# lab1_kondratchenko_usb_rs485.net
KiCad netlist of a schematic drawn in Altium Designer
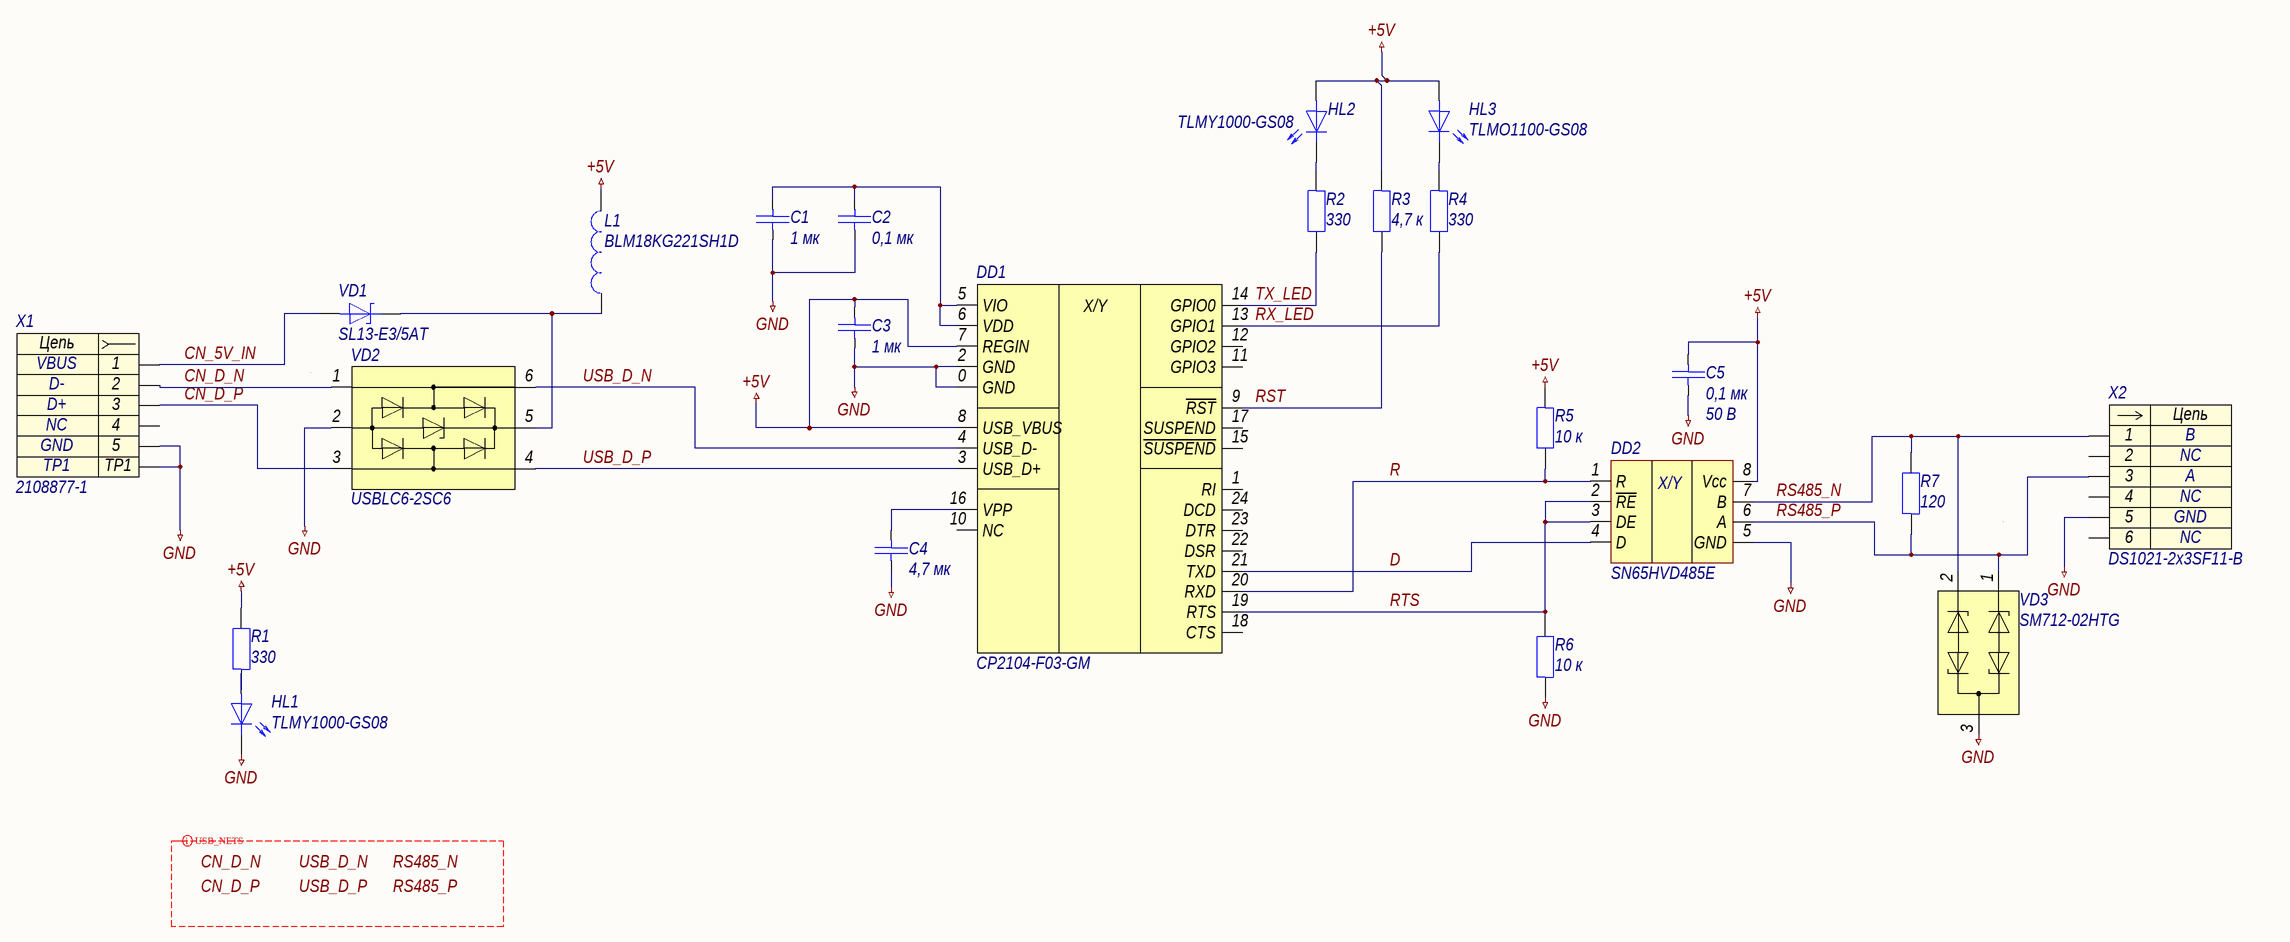
[diagram p0: lab1_kondratchenko_usb_rs485.SchDoc]

(export (version "E")
  (design (tool "Eeschema 10.0.6"))
  (components
    (comp (ref "C1")
      (value "1 мк")
      (footprint "C0603")
      (description "=Описание")
      (libsource (lib "Database_Students") (part "CAPACITOR-NONPOLAR"))
    )
    (comp (ref "C2")
      (value "0,1 мк")
      (footprint "C0603")
      (description "=Описание")
      (libsource (lib "Database_Students") (part "CAPACITOR-NONPOLAR"))
    )
    (comp (ref "C3")
      (value "1 мк")
      (footprint "C0603")
      (description "=Описание")
      (libsource (lib "Database_Students") (part "CAPACITOR-NONPOLAR"))
    )
    (comp (ref "C4")
      (value "4,7 мк")
      (footprint "C0603")
      (description "=Описание")
      (libsource (lib "Database_Students") (part "CAPACITOR-NONPOLAR"))
    )
    (comp (ref "C5")
      (value "0,1 мк")
      (footprint "C0603")
      (description "=Описание")
      (fields (field (name "НАПРЯЖЕНИЕ") "50 В"))
      (libsource (lib "Database_Students") (part "CAPACITOR-NONPOLAR"))
    )
    (comp (ref "DD1")
      (value "CP2104-F03-GM")
      (footprint "QFN-24-400X400X80")
      (description "=Описание")
      (libsource (lib "Database_Students") (part "CP2104-F03-GM"))
    )
    (comp (ref "DD2")
      (value "SN65HVD485E")
      (footprint "D0008A")
      (description "=Описание")
      (libsource (lib "SN65HVD485E") (part "SN65HVD485E"))
    )
    (comp (ref "HL1")
      (value "TLMY1000-GS08")
      (footprint "HL0603")
      (description "=Описание")
      (libsource (lib "Database_Students") (part "LED-COMMON"))
    )
    (comp (ref "HL2")
      (value "TLMY1000-GS08")
      (footprint "HL0603")
      (description "=Описание")
      (libsource (lib "Database_Students") (part "LED-COMMON"))
    )
    (comp (ref "HL3")
      (value "TLMO1100-GS08")
      (footprint "HL0603")
      (description "=Описание")
      (libsource (lib "Database_Students") (part "LED-COMMON"))
    )
    (comp (ref "L1")
      (value "BLM18KG221SH1D")
      (footprint "BLM-2-0603")
      (description "=Описание")
      (libsource (lib "Database_Students") (part "FERRITE-BEAD"))
    )
    (comp (ref "R1")
      (value "330")
      (footprint "R0603")
      (description "=Описание")
      (libsource (lib "Database_Students") (part "R-COMMON"))
    )
    (comp (ref "R2")
      (value "330")
      (footprint "R0603")
      (description "=Описание")
      (libsource (lib "Database_Students") (part "RESISTOR-COMMON"))
    )
    (comp (ref "R3")
      (value "4,7 к")
      (footprint "R0603")
      (description "=Описание")
      (libsource (lib "Database_Students") (part "RESISTOR-COMMON"))
    )
    (comp (ref "R4")
      (value "330")
      (footprint "R0603")
      (description "=Описание")
      (libsource (lib "Database_Students") (part "RESISTOR-COMMON"))
    )
    (comp (ref "R5")
      (value "10 к")
      (footprint "R0603")
      (description "=Описание")
      (libsource (lib "Database_Students") (part "RESISTOR-COMMON"))
    )
    (comp (ref "R6")
      (value "10 к")
      (footprint "R0603")
      (description "=Описание")
      (libsource (lib "Database_Students") (part "RESISTOR-COMMON"))
    )
    (comp (ref "R7")
      (value "120")
      (footprint "R0603")
      (description "=Описание")
      (libsource (lib "Database_Students") (part "R-COMMON"))
    )
    (comp (ref "VD1")
      (value "SL13-E3/5AT")
      (footprint "DO-214AC")
      (description "=Описание")
      (libsource (lib "Database_Students") (part "DIODE-SCHOTTKY"))
    )
    (comp (ref "VD2")
      (value "USBLC6-2SC6")
      (footprint "SOT-23-6")
      (description "=Описание")
      (libsource (lib "Database_Students") (part "USBLC6-2SC6"))
    )
    (comp (ref "VD3")
      (value "SM712-02HTG")
      (footprint "SOT-23-3")
      (description "=Описание")
      (libsource (lib "Database_Students") (part "SM712-02HTG"))
    )
    (comp (ref "X1")
      (value "2108877-1")
      (footprint "2108877-1")
      (libsource (lib "Database_Students") (part "HEADER-5-TP1-SCT"))
    )
    (comp (ref "X2")
      (value "DS1021-2x3SF11-B")
      (footprint "DS1021-2X3SF11-B")
      (description "=Описание")
      (libsource (lib "Database_Students") (part "HEADER-6-PLG"))
    )
  )
  (nets
    (net (code "1") (name "+5V") (class "Default")
      (node (ref "C3") (pin "2") (pinfunction "2_2") (pintype "passive"))
      (node (ref "C5") (pin "2") (pinfunction "2_2") (pintype "passive"))
      (node (ref "DD1") (pin "7") (pinfunction "REGIN_7") (pintype "passive"))
      (node (ref "DD1") (pin "8") (pinfunction "USB_VBUS_8") (pintype "passive"))
      (node (ref "DD2") (pin "8") (pinfunction "Vcc_8") (pintype "passive"))
      (node (ref "HL2") (pin "2") (pinfunction "2_2") (pintype "passive"))
      (node (ref "HL3") (pin "2") (pinfunction "2_2") (pintype "passive"))
      (node (ref "L1") (pin "2") (pinfunction "2_2") (pintype "passive"))
      (node (ref "R1") (pin "2") (pinfunction "2_2") (pintype "passive"))
      (node (ref "R3") (pin "1") (pinfunction "1_1") (pintype "passive"))
      (node (ref "R5") (pin "1") (pinfunction "1_1") (pintype "passive"))
    )
    (net (code "2") (name "/CN_5V_IN") (class "Default")
      (node (ref "VD1") (pin "2") (pinfunction "2_2") (pintype "passive"))
      (node (ref "X1") (pin "1") (pinfunction "1_1") (pintype "passive"))
    )
    (net (code "3") (name "/CN_D_N") (class "Default")
      (node (ref "VD2") (pin "1") (pinfunction "1_1") (pintype "passive"))
      (node (ref "X1") (pin "2") (pinfunction "2_2") (pintype "passive"))
    )
    (net (code "4") (name "/CN_D_P") (class "Default")
      (node (ref "VD2") (pin "3") (pinfunction "3_3") (pintype "passive"))
      (node (ref "X1") (pin "3") (pinfunction "3_3") (pintype "passive"))
    )
    (net (code "5") (name "/D") (class "Default")
      (node (ref "DD1") (pin "21") (pinfunction "TXD_21") (pintype "passive"))
      (node (ref "DD2") (pin "4") (pinfunction "D_4") (pintype "passive"))
    )
    (net (code "6") (name "/R") (class "Default")
      (node (ref "DD1") (pin "20") (pinfunction "RXD_20") (pintype "passive"))
      (node (ref "DD2") (pin "1") (pinfunction "R_1") (pintype "passive"))
      (node (ref "R5") (pin "2") (pinfunction "2_2") (pintype "passive"))
    )
    (net (code "7") (name "/RS485_N") (class "Default")
      (node (ref "DD2") (pin "7") (pinfunction "B_7") (pintype "passive"))
      (node (ref "R7") (pin "2") (pinfunction "2_2") (pintype "passive"))
      (node (ref "VD3") (pin "2") (pinfunction "2_2") (pintype "passive"))
      (node (ref "X2") (pin "1") (pinfunction "1_1") (pintype "passive"))
    )
    (net (code "8") (name "/RS485_P") (class "Default")
      (node (ref "DD2") (pin "6") (pinfunction "A_6") (pintype "passive"))
      (node (ref "R7") (pin "1") (pinfunction "1_1") (pintype "passive"))
      (node (ref "VD3") (pin "1") (pinfunction "1_1") (pintype "passive"))
      (node (ref "X2") (pin "3") (pinfunction "3_3") (pintype "passive"))
    )
    (net (code "9") (name "/RST") (class "Default")
      (node (ref "DD1") (pin "9") (pinfunction "~{RST}_9") (pintype "passive"))
      (node (ref "R3") (pin "2") (pinfunction "2_2") (pintype "passive"))
    )
    (net (code "10") (name "/RTS") (class "Default")
      (node (ref "DD1") (pin "19") (pinfunction "RTS_19") (pintype "passive"))
      (node (ref "DD2") (pin "2") (pinfunction "~{RE}_2") (pintype "passive"))
      (node (ref "DD2") (pin "3") (pinfunction "DE_3") (pintype "passive"))
      (node (ref "R6") (pin "2") (pinfunction "2_2") (pintype "passive"))
    )
    (net (code "11") (name "/RX_LED") (class "Default")
      (node (ref "DD1") (pin "13") (pinfunction "GPIO1_13") (pintype "passive"))
      (node (ref "R4") (pin "2") (pinfunction "2_2") (pintype "passive"))
    )
    (net (code "12") (name "/TX_LED") (class "Default")
      (node (ref "DD1") (pin "14") (pinfunction "GPIO0_14") (pintype "passive"))
      (node (ref "R2") (pin "2") (pinfunction "2_2") (pintype "passive"))
    )
    (net (code "13") (name "/USB_D_N") (class "Default")
      (node (ref "DD1") (pin "4") (pinfunction "USB_D-_4") (pintype "passive"))
      (node (ref "VD2") (pin "6") (pinfunction "6_6") (pintype "passive"))
    )
    (net (code "14") (name "/USB_D_P") (class "Default")
      (node (ref "DD1") (pin "3") (pinfunction "USB_D+_3") (pintype "passive"))
      (node (ref "VD2") (pin "4") (pinfunction "4_4") (pintype "passive"))
    )
    (net (code "15") (name "GND") (class "Default")
      (node (ref "C1") (pin "1") (pinfunction "1_1") (pintype "passive"))
      (node (ref "C2") (pin "1") (pinfunction "1_1") (pintype "passive"))
      (node (ref "C3") (pin "1") (pinfunction "1_1") (pintype "passive"))
      (node (ref "C4") (pin "1") (pinfunction "1_1") (pintype "passive"))
      (node (ref "C5") (pin "1") (pinfunction "1_1") (pintype "passive"))
      (node (ref "DD1") (pin "0") (pinfunction "GND_0") (pintype "passive"))
      (node (ref "DD1") (pin "2") (pinfunction "GND_2") (pintype "passive"))
      (node (ref "DD2") (pin "5") (pinfunction "GND_5") (pintype "passive"))
      (node (ref "HL1") (pin "1") (pinfunction "1_1") (pintype "passive"))
      (node (ref "R6") (pin "1") (pinfunction "1_1") (pintype "passive"))
      (node (ref "VD2") (pin "2") (pinfunction "2_2") (pintype "passive"))
      (node (ref "VD3") (pin "3") (pinfunction "3_3") (pintype "passive"))
      (node (ref "X1") (pin "5") (pinfunction "5_5") (pintype "passive"))
      (node (ref "X1") (pin "TP1") (pinfunction "TP1_TP1") (pintype "passive"))
      (node (ref "X2") (pin "5") (pinfunction "5_5") (pintype "passive"))
    )
    (net (code "16") (name "Net-(DD1-VDD)") (class "Default")
      (node (ref "C1") (pin "2") (pinfunction "2_2") (pintype "passive"))
      (node (ref "C2") (pin "2") (pinfunction "2_2") (pintype "passive"))
      (node (ref "DD1") (pin "5") (pinfunction "VIO_5") (pintype "passive"))
      (node (ref "DD1") (pin "6") (pinfunction "VDD_6") (pintype "passive"))
    )
    (net (code "17") (name "Net-(DD1-VPP)") (class "Default")
      (node (ref "C4") (pin "2") (pinfunction "2_2") (pintype "passive"))
      (node (ref "DD1") (pin "16") (pinfunction "VPP_16") (pintype "passive"))
    )
    (net (code "18") (name "Net-(HL1-Pad2)") (class "Default")
      (node (ref "HL1") (pin "2") (pinfunction "2_2") (pintype "passive"))
      (node (ref "R1") (pin "1") (pinfunction "1_1") (pintype "passive"))
    )
    (net (code "19") (name "Net-(HL2-Pad1)") (class "Default")
      (node (ref "HL2") (pin "1") (pinfunction "1_1") (pintype "passive"))
      (node (ref "R2") (pin "1") (pinfunction "1_1") (pintype "passive"))
    )
    (net (code "20") (name "Net-(HL3-Pad1)") (class "Default")
      (node (ref "HL3") (pin "1") (pinfunction "1_1") (pintype "passive"))
      (node (ref "R4") (pin "1") (pinfunction "1_1") (pintype "passive"))
    )
    (net (code "21") (name "Net-(L1-Pad1)") (class "Default")
      (node (ref "L1") (pin "1") (pinfunction "1_1") (pintype "passive"))
      (node (ref "VD1") (pin "1") (pinfunction "1_1") (pintype "passive"))
      (node (ref "VD2") (pin "5") (pinfunction "5_5") (pintype "passive"))
    )
    (net (code "22") (name "unconnected-(DD1-CTS-Pad18)") (class "Default")
      (node (ref "DD1") (pin "18") (pinfunction "CTS_18") (pintype "passive"))
    )
    (net (code "23") (name "unconnected-(DD1-DCD-Pad24)") (class "Default")
      (node (ref "DD1") (pin "24") (pinfunction "DCD_24") (pintype "passive"))
    )
    (net (code "24") (name "unconnected-(DD1-DSR-Pad22)") (class "Default")
      (node (ref "DD1") (pin "22") (pinfunction "DSR_22") (pintype "passive"))
    )
    (net (code "25") (name "unconnected-(DD1-DTR-Pad23)") (class "Default")
      (node (ref "DD1") (pin "23") (pinfunction "DTR_23") (pintype "passive"))
    )
    (net (code "26") (name "unconnected-(DD1-GPIO2-Pad12)") (class "Default")
      (node (ref "DD1") (pin "12") (pinfunction "GPIO2_12") (pintype "passive"))
    )
    (net (code "27") (name "unconnected-(DD1-GPIO3-Pad11)") (class "Default")
      (node (ref "DD1") (pin "11") (pinfunction "GPIO3_11") (pintype "passive"))
    )
    (net (code "28") (name "unconnected-(DD1-NC-Pad10)") (class "Default")
      (node (ref "DD1") (pin "10") (pinfunction "NC_10") (pintype "passive"))
    )
    (net (code "29") (name "unconnected-(DD1-RI-Pad1)") (class "Default")
      (node (ref "DD1") (pin "1") (pinfunction "RI_1") (pintype "passive"))
    )
    (net (code "30") (name "unconnected-(DD1-SUSPEND-Pad17)") (class "Default")
      (node (ref "DD1") (pin "17") (pinfunction "SUSPEND_17") (pintype "passive"))
    )
    (net (code "31") (name "unconnected-(DD1-~{SUSPEND}-Pad15)") (class "Default")
      (node (ref "DD1") (pin "15") (pinfunction "~{SUSPEND}_15") (pintype "passive"))
    )
    (net (code "32") (name "unconnected-(X1-Pad4)") (class "Default")
      (node (ref "X1") (pin "4") (pinfunction "4_4") (pintype "passive"))
    )
    (net (code "33") (name "unconnected-(X2-Pad2)") (class "Default")
      (node (ref "X2") (pin "2") (pinfunction "2_2") (pintype "passive"))
    )
    (net (code "34") (name "unconnected-(X2-Pad4)") (class "Default")
      (node (ref "X2") (pin "4") (pinfunction "4_4") (pintype "passive"))
    )
    (net (code "35") (name "unconnected-(X2-Pad6)") (class "Default")
      (node (ref "X2") (pin "6") (pinfunction "6_6") (pintype "passive"))
    )
  )
)
